# rapidshark-flywheel-controller-mk-1_5.net
KiCad netlist of a schematic drawn in EAGLE
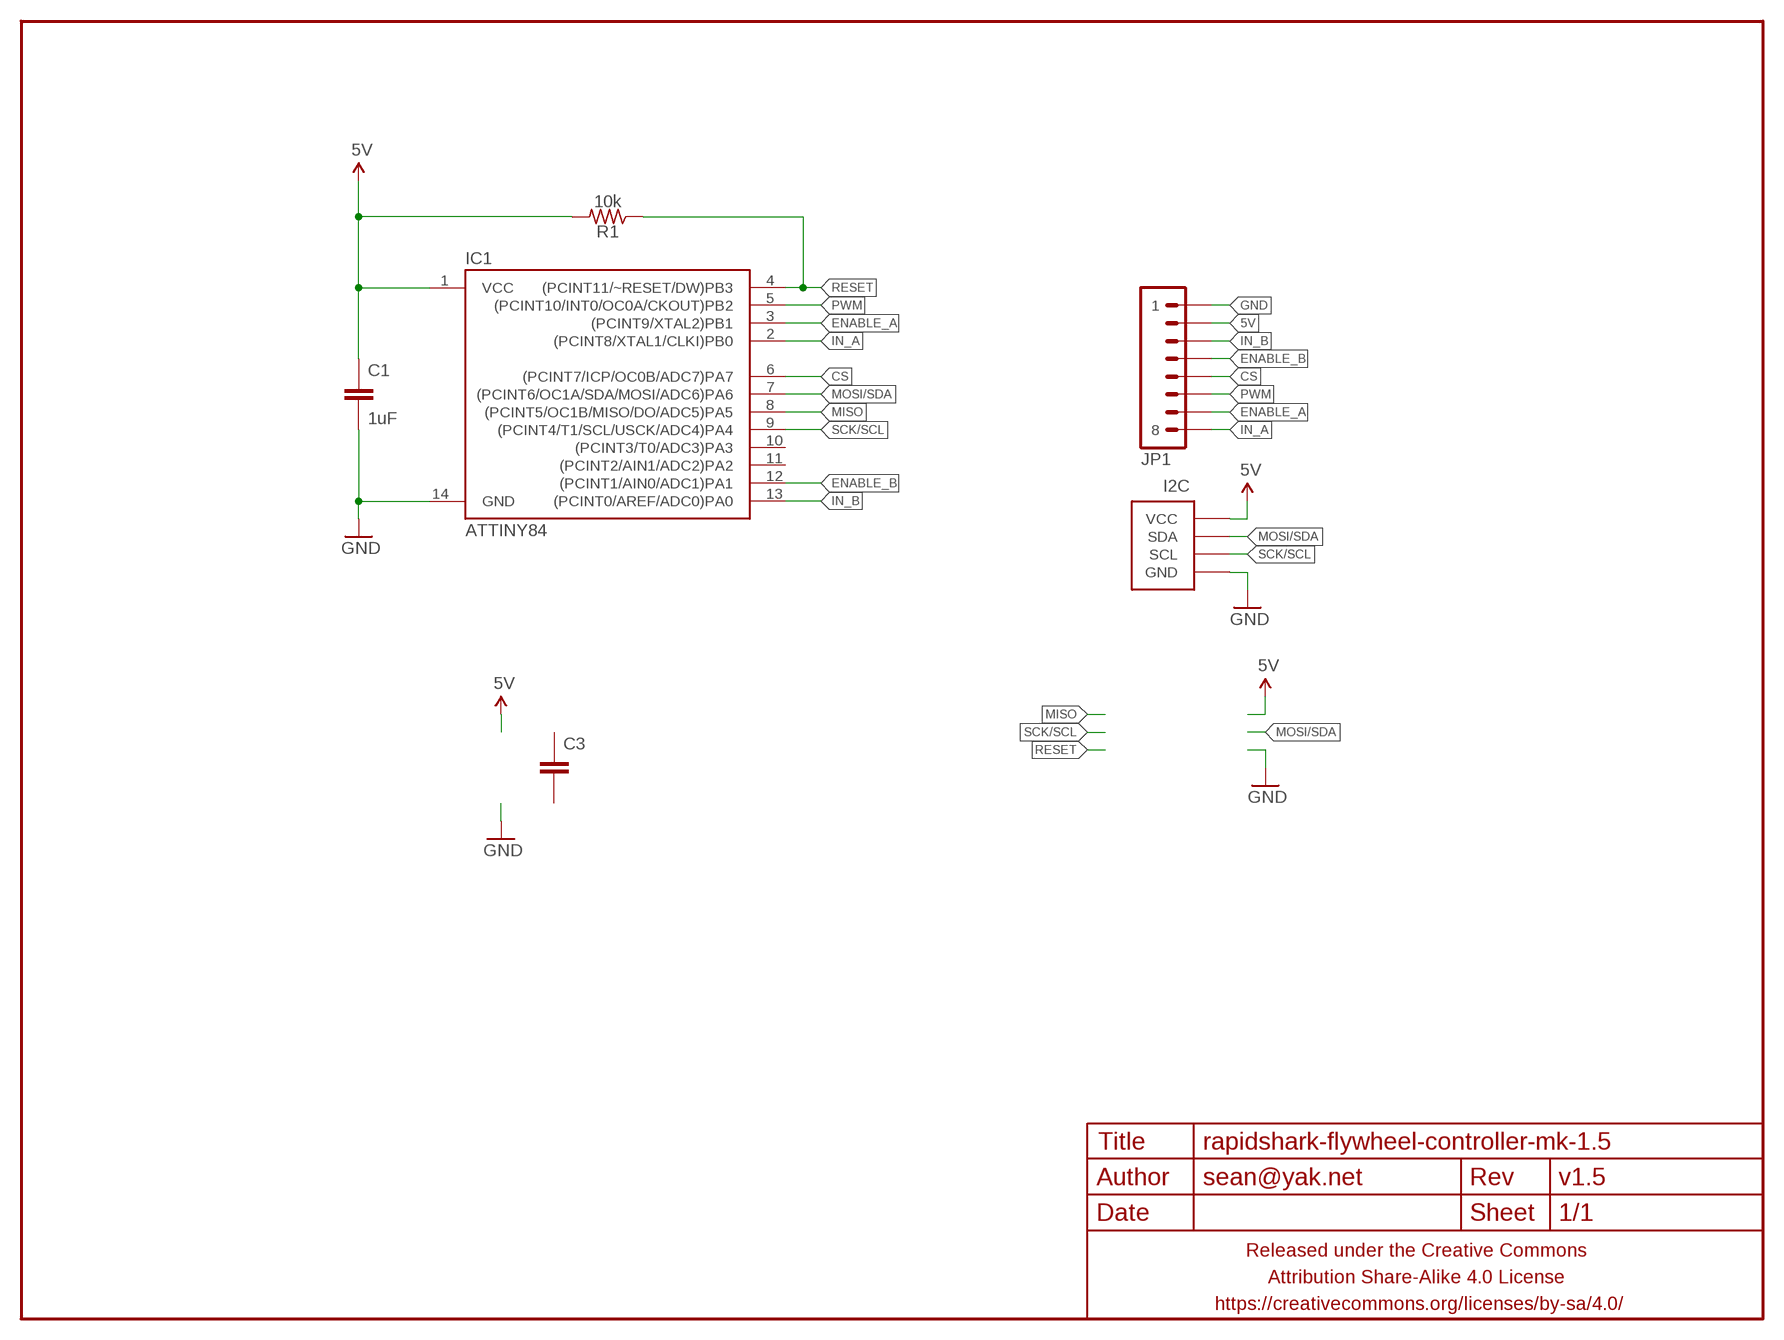
[diagram p0: schematic, sheet 1]

(export (version "E")
  (design (tool "Eeschema 10.0.6"))
  (components
    (comp (ref "C1")
      (value "1uF")
      (footprint "eagle-import:C0603-TIGHTER")
      (libsource (lib "eagle-import") (part "CAPACITOR-CERAMICC0603-TIGHTER"))
    )
    (comp (ref "C3")
      (value "CAPACITOR-CERAMICC0603-TIGHTER")
      (footprint "eagle-import:C0603-TIGHTER")
      (libsource (lib "eagle-import") (part "CAPACITOR-CERAMICC0603-TIGHTER"))
    )
    (comp (ref "FRAME1")
      (value "FRAME-LETTERNO_PACKAGE")
      (footprint "eagle-import:DUMMY")
      (fields (field (name "DESIGNER") "sean@yak.net") (field (name "VERSION") "v1.5"))
      (libsource (lib "eagle-import") (part "FRAME-LETTERNO_PACKAGE"))
    )
    (comp (ref "I2C")
      (value "M04-I2CJST-4-PH-RA-CENTERED")
      (footprint "eagle-import:1X04-JST-PH-RA-PTH-I2C-CENTERED")
      (libsource (lib "eagle-import") (part "M04-I2CJST-4-PH-RA-CENTERED"))
    )
    (comp (ref "IC1")
      (value "ATTINY84")
      (footprint "eagle-import:SO14")
      (libsource (lib "eagle-import") (part "ATTINY84"))
    )
    (comp (ref "JP1")
      (value "M081X08")
      (footprint "eagle-import:1X08")
      (libsource (lib "eagle-import") (part "M081X08"))
    )
    (comp (ref "R1")
      (value "10k")
      (footprint "eagle-import:RESISTOR-AXIAL-PTH-5.08MM")
      (libsource (lib "eagle-import") (part "RESISTORPTH-AXIAL-5.08MM"))
    )
  )
  (nets
    (net (code "1") (name "5V") (class "Default")
      (node (ref "C1") (pin "1") (pinfunction "1_1") (pintype "passive"))
      (node (ref "I2C") (pin "2") (pinfunction "VCC_2") (pintype "bidirectional"))
      (node (ref "IC1") (pin "1") (pinfunction "VCC_1") (pintype "bidirectional"))
      (node (ref "JP1") (pin "2") (pinfunction "2_2") (pintype "passive"))
      (node (ref "R1") (pin "P$2") (pinfunction "2_P$2") (pintype "passive"))
    )
    (net (code "2") (name "CS") (class "Default")
      (node (ref "IC1") (pin "6") (pinfunction "(PCINT7/ICP/OC0B/ADC7)PA7_6") (pintype "bidirectional"))
      (node (ref "JP1") (pin "5") (pinfunction "5_5") (pintype "passive"))
    )
    (net (code "3") (name "ENABLE_A") (class "Default")
      (node (ref "IC1") (pin "3") (pinfunction "(PCINT9/XTAL2)PB1_3") (pintype "bidirectional"))
      (node (ref "JP1") (pin "7") (pinfunction "7_7") (pintype "passive"))
    )
    (net (code "4") (name "ENABLE_B") (class "Default")
      (node (ref "IC1") (pin "12") (pinfunction "(PCINT1/AIN0/ADC1)PA1_12") (pintype "bidirectional"))
      (node (ref "JP1") (pin "4") (pinfunction "4_4") (pintype "passive"))
    )
    (net (code "5") (name "GND") (class "Default")
      (node (ref "C1") (pin "2") (pinfunction "2_2") (pintype "passive"))
      (node (ref "I2C") (pin "1") (pinfunction "GND_1") (pintype "bidirectional"))
      (node (ref "IC1") (pin "14") (pinfunction "GND_14") (pintype "bidirectional"))
      (node (ref "JP1") (pin "1") (pinfunction "1_1") (pintype "passive"))
    )
    (net (code "6") (name "IN_A") (class "Default")
      (node (ref "IC1") (pin "2") (pinfunction "(PCINT8/XTAL1/CLKI)PB0_2") (pintype "bidirectional"))
      (node (ref "JP1") (pin "8") (pinfunction "8_8") (pintype "passive"))
    )
    (net (code "7") (name "IN_B") (class "Default")
      (node (ref "IC1") (pin "13") (pinfunction "(PCINT0/AREF/ADC0)PA0_13") (pintype "bidirectional"))
      (node (ref "JP1") (pin "3") (pinfunction "3_3") (pintype "passive"))
    )
    (net (code "8") (name "MISO") (class "Default")
      (node (ref "IC1") (pin "8") (pinfunction "(PCINT5/OC1B/MISO/DO/ADC5)PA5_8") (pintype "bidirectional"))
    )
    (net (code "9") (name "MOSI{slash}SDA") (class "Default")
      (node (ref "I2C") (pin "3") (pinfunction "SDA_3") (pintype "bidirectional"))
      (node (ref "IC1") (pin "7") (pinfunction "(PCINT6/OC1A/SDA/MOSI/ADC6)PA6_7") (pintype "bidirectional"))
    )
    (net (code "10") (name "PWM") (class "Default")
      (node (ref "IC1") (pin "5") (pinfunction "(PCINT10/INT0/OC0A/CKOUT)PB2_5") (pintype "bidirectional"))
      (node (ref "JP1") (pin "6") (pinfunction "6_6") (pintype "passive"))
    )
    (net (code "11") (name "RESET") (class "Default")
      (node (ref "IC1") (pin "4") (pinfunction "(PCINT11/~{RESET/DW})PB3_4") (pintype "bidirectional"))
      (node (ref "R1") (pin "P$1") (pinfunction "1_P$1") (pintype "passive"))
    )
    (net (code "12") (name "SCK{slash}SCL") (class "Default")
      (node (ref "I2C") (pin "4") (pinfunction "SCL_4") (pintype "bidirectional"))
      (node (ref "IC1") (pin "9") (pinfunction "(PCINT4/T1/SCL/USCK/ADC4)PA4_9") (pintype "bidirectional"))
    )
    (net (code "13") (name "unconnected-(C3-Pad1)") (class "Default")
      (node (ref "C3") (pin "1") (pinfunction "1_1") (pintype "passive"))
    )
    (net (code "14") (name "unconnected-(C3-Pad2)") (class "Default")
      (node (ref "C3") (pin "2") (pinfunction "2_2") (pintype "passive"))
    )
    (net (code "15") (name "unconnected-(IC1-(PCINT2{slash}AIN1{slash}ADC2)PA2-Pad11)") (class "Default")
      (node (ref "IC1") (pin "11") (pinfunction "(PCINT2/AIN1/ADC2)PA2_11") (pintype "bidirectional"))
    )
    (net (code "16") (name "unconnected-(IC1-(PCINT3{slash}T0{slash}ADC3)PA3-Pad10)") (class "Default")
      (node (ref "IC1") (pin "10") (pinfunction "(PCINT3/T0/ADC3)PA3_10") (pintype "bidirectional"))
    )
  )
)
